# MCU.net
KiCad netlist of a schematic drawn in Altium Designer
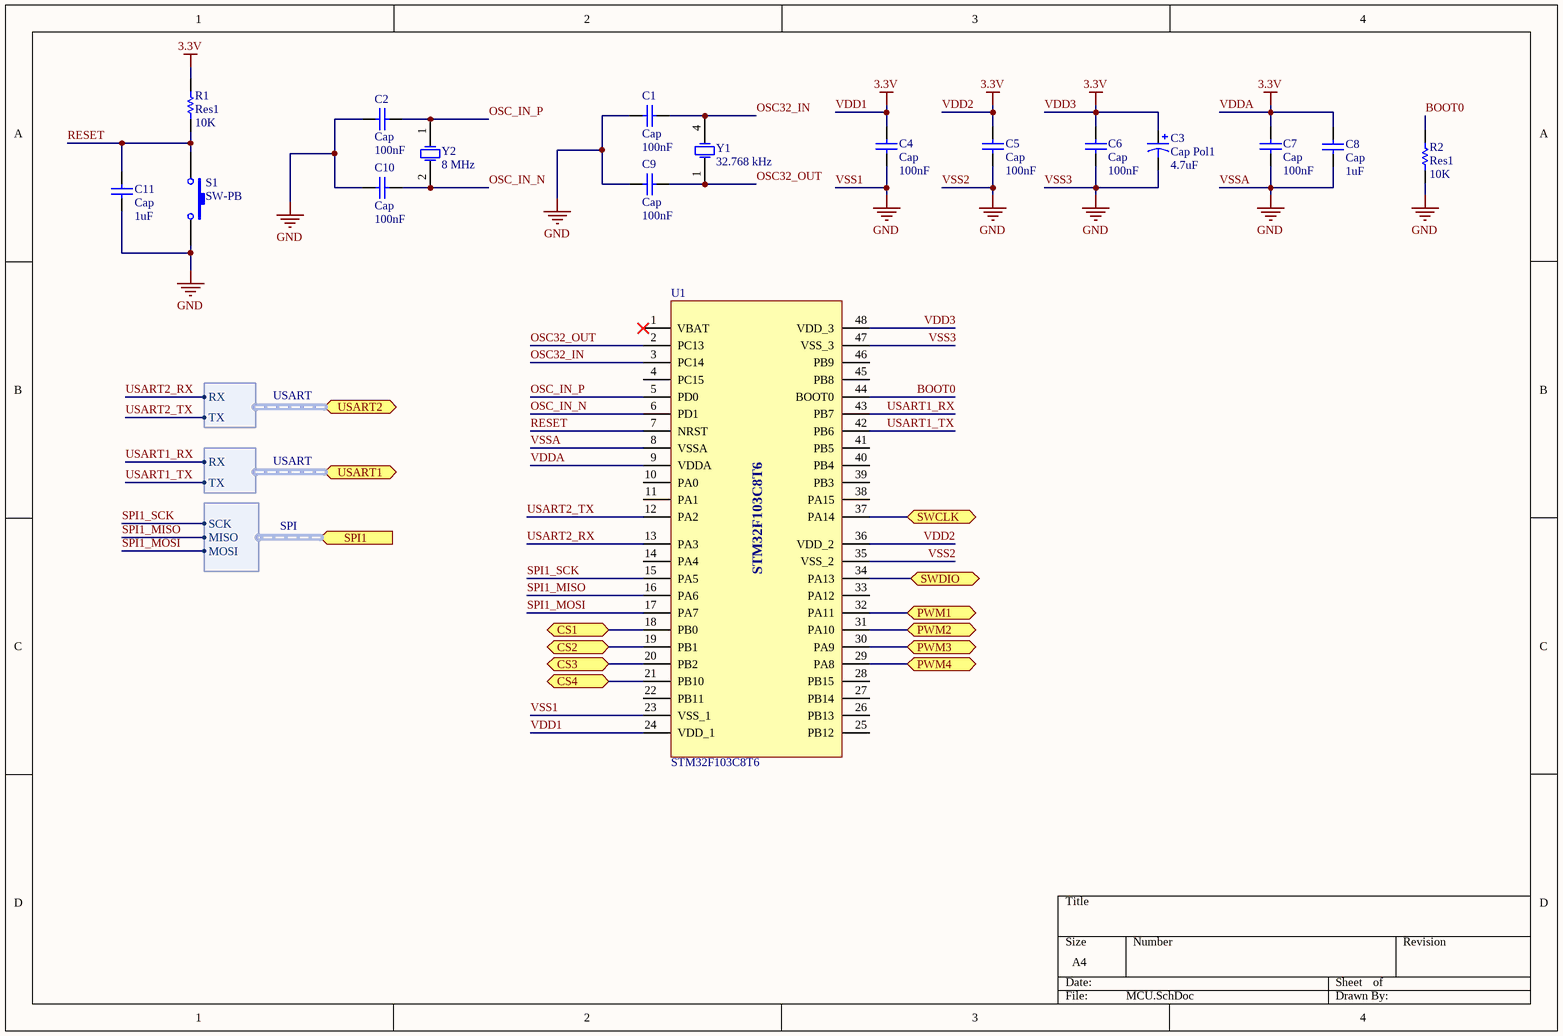
[diagram p0: MCU.SchDoc]

(export (version "E")
  (design (tool "Eeschema 10.0.6"))
  (components
    (comp (ref "C1")
      (value "Cap")
      (footprint "0805-CAP")
      (description "Capacitor")
      (fields (field (name "ALTIUM_VALUE") "100nF") (field (name "PUBLISHER") "Altium Limited"))
      (libsource (lib "Miscellaneous Devices") (part "Cap"))
    )
    (comp (ref "C2")
      (value "Cap")
      (footprint "0805-CAP")
      (description "Capacitor")
      (fields (field (name "ALTIUM_VALUE") "100nF") (field (name "PUBLISHER") "Altium Limited"))
      (libsource (lib "Miscellaneous Devices") (part "Cap"))
    )
    (comp (ref "C3")
      (value "Cap Pol1")
      (footprint "Tantalum A-Case")
      (description "Polarized Capacitor (Radial)")
      (fields (field (name "ALTIUM_VALUE") "4.7uF") (field (name "PUBLISHER") "Altium Limited"))
      (libsource (lib "Miscellaneous Devices") (part "Cap Pol1"))
    )
    (comp (ref "C4")
      (value "Cap")
      (footprint "0805-CAP")
      (description "Capacitor")
      (fields (field (name "ALTIUM_VALUE") "100nF") (field (name "PUBLISHER") "Altium Limited"))
      (libsource (lib "Miscellaneous Devices") (part "Cap"))
    )
    (comp (ref "C5")
      (value "Cap")
      (footprint "0805-CAP")
      (description "Capacitor")
      (fields (field (name "ALTIUM_VALUE") "100nF") (field (name "PUBLISHER") "Altium Limited"))
      (libsource (lib "Miscellaneous Devices") (part "Cap"))
    )
    (comp (ref "C6")
      (value "Cap")
      (footprint "0805-CAP")
      (description "Capacitor")
      (fields (field (name "ALTIUM_VALUE") "100nF") (field (name "PUBLISHER") "Altium Limited"))
      (libsource (lib "Miscellaneous Devices") (part "Cap"))
    )
    (comp (ref "C7")
      (value "Cap")
      (footprint "0805-CAP")
      (description "Capacitor")
      (fields (field (name "ALTIUM_VALUE") "100nF") (field (name "PUBLISHER") "Altium Limited"))
      (libsource (lib "Miscellaneous Devices") (part "Cap"))
    )
    (comp (ref "C8")
      (value "Cap")
      (footprint "0805-CAP")
      (description "Capacitor")
      (fields (field (name "ALTIUM_VALUE") "1uF") (field (name "PUBLISHER") "Altium Limited"))
      (libsource (lib "Miscellaneous Devices") (part "Cap"))
    )
    (comp (ref "C9")
      (value "Cap")
      (footprint "0805-CAP")
      (description "Capacitor")
      (fields (field (name "ALTIUM_VALUE") "100nF") (field (name "PUBLISHER") "Altium Limited"))
      (libsource (lib "Miscellaneous Devices") (part "Cap"))
    )
    (comp (ref "C10")
      (value "Cap")
      (footprint "0805-CAP")
      (description "Capacitor")
      (fields (field (name "ALTIUM_VALUE") "100nF") (field (name "PUBLISHER") "Altium Limited"))
      (libsource (lib "Miscellaneous Devices") (part "Cap"))
    )
    (comp (ref "C11")
      (value "Cap")
      (footprint "0805-CAP")
      (description "Capacitor")
      (fields (field (name "ALTIUM_VALUE") "1uF") (field (name "PUBLISHER") "Altium Limited"))
      (libsource (lib "Miscellaneous Devices") (part "Cap"))
    )
    (comp (ref "R1")
      (value "Res1")
      (footprint "0805-RES")
      (description "Resistor")
      (fields (field (name "ALTIUM_VALUE") "10K") (field (name "PUBLISHER") "Altium Limited"))
      (libsource (lib "Miscellaneous Devices") (part "Res1"))
    )
    (comp (ref "R2")
      (value "Res1")
      (footprint "0805-RES")
      (description "Resistor")
      (fields (field (name "ALTIUM_VALUE") "10K") (field (name "PUBLISHER") "Altium Limited"))
      (libsource (lib "Miscellaneous Devices") (part "Res1"))
    )
    (comp (ref "S1")
      (value "SW-PB")
      (footprint "3x6x2.5mm Tacticle Push Button")
      (description "Switch")
      (fields (field (name "PUBLISHER") "Altium Limited"))
      (libsource (lib "Miscellaneous Devices") (part "SW-PB"))
    )
    (comp (ref "U1")
      (value "STM32F103C8T6")
      (footprint "LQFP-48")
      (description "STM32F103C8T6 LQPF-48")
      (libsource (lib "MCU-Schematics") (part "STM32F103C8T6-LQPF48"))
    )
    (comp (ref "Y1")
      (value "32.768 kHz")
      (footprint "MC-306 SMD")
      (description "Crystal Oscillator")
      (fields (field (name "PUBLISHER") "Altium Limited"))
      (libsource (lib "Miscellaneous Devices") (part "XTAL"))
    )
    (comp (ref "Y2")
      (value "8 MHz")
      (footprint "HC49 Crystal SMD")
      (description "Crystal Oscillator")
      (fields (field (name "PUBLISHER") "Altium Limited"))
      (libsource (lib "") (part "XTAL_1"))
    )
  )
  (nets
    (net (code "3") (name "/BOOT0") (class "Default")
      (node (ref "R2") (pin "2") (pinfunction "2_2") (pintype "passive"))
      (node (ref "U1") (pin "44") (pinfunction "BOOT0_44") (pintype "passive"))
    )
    (net (code "4") (name "/CS1") (class "Default")
      (node (ref "U1") (pin "18") (pinfunction "PB0_18") (pintype "passive"))
    )
    (net (code "5") (name "/CS2") (class "Default")
      (node (ref "U1") (pin "19") (pinfunction "PB1_19") (pintype "passive"))
    )
    (net (code "6") (name "/CS3") (class "Default")
      (node (ref "U1") (pin "20") (pinfunction "PB2_20") (pintype "passive"))
    )
    (net (code "7") (name "/CS4") (class "Default")
      (node (ref "U1") (pin "21") (pinfunction "PB10_21") (pintype "passive"))
    )
    (net (code "8") (name "/OSC32_IN") (class "Default")
      (node (ref "C1") (pin "1") (pinfunction "1_1") (pintype "passive"))
      (node (ref "U1") (pin "3") (pinfunction "PC14_3") (pintype "passive"))
      (node (ref "Y1") (pin "4") (pinfunction "OSC2_4") (pintype "passive"))
    )
    (net (code "9") (name "/OSC32_OUT") (class "Default")
      (node (ref "C9") (pin "1") (pinfunction "1_1") (pintype "passive"))
      (node (ref "U1") (pin "2") (pinfunction "PC13_2") (pintype "passive"))
      (node (ref "Y1") (pin "1") (pinfunction "OSC1_1") (pintype "passive"))
    )
    (net (code "10") (name "/OSC_IN_N") (class "Default")
      (node (ref "C10") (pin "1") (pinfunction "1_1") (pintype "passive"))
      (node (ref "U1") (pin "6") (pinfunction "PD1_6") (pintype "passive"))
      (node (ref "Y2") (pin "2") (pinfunction "OSC2_2") (pintype "passive"))
    )
    (net (code "11") (name "/OSC_IN_P") (class "Default")
      (node (ref "C2") (pin "1") (pinfunction "1_1") (pintype "passive"))
      (node (ref "U1") (pin "5") (pinfunction "PD0_5") (pintype "passive"))
      (node (ref "Y2") (pin "1") (pinfunction "OSC1_1") (pintype "passive"))
    )
    (net (code "12") (name "/PWM1") (class "Default")
      (node (ref "U1") (pin "32") (pinfunction "PA11_32") (pintype "passive"))
    )
    (net (code "13") (name "/PWM2") (class "Default")
      (node (ref "U1") (pin "31") (pinfunction "PA10_31") (pintype "passive"))
    )
    (net (code "14") (name "/PWM3") (class "Default")
      (node (ref "U1") (pin "30") (pinfunction "PA9_30") (pintype "passive"))
    )
    (net (code "15") (name "/PWM4") (class "Default")
      (node (ref "U1") (pin "29") (pinfunction "PA8_29") (pintype "passive"))
    )
    (net (code "16") (name "/RESET") (class "Default")
      (node (ref "C11") (pin "2") (pinfunction "2_2") (pintype "passive"))
      (node (ref "R1") (pin "1") (pinfunction "1_1") (pintype "passive"))
      (node (ref "S1") (pin "1") (pinfunction "1_1") (pintype "passive"))
      (node (ref "U1") (pin "7") (pinfunction "NRST_7") (pintype "passive"))
    )
    (net (code "17") (name "/SPI1_MISO") (class "Default")
      (node (ref "U1") (pin "16") (pinfunction "PA6_16") (pintype "passive"))
    )
    (net (code "18") (name "/SPI1_MOSI") (class "Default")
      (node (ref "U1") (pin "17") (pinfunction "PA7_17") (pintype "passive"))
    )
    (net (code "19") (name "/SPI1_SCK") (class "Default")
      (node (ref "U1") (pin "15") (pinfunction "PA5_15") (pintype "passive"))
    )
    (net (code "20") (name "/SWCLK") (class "Default")
      (node (ref "U1") (pin "37") (pinfunction "PA14_37") (pintype "passive"))
    )
    (net (code "21") (name "/SWDIO") (class "Default")
      (node (ref "U1") (pin "34") (pinfunction "PA13_34") (pintype "passive"))
    )
    (net (code "22") (name "/USART1_RX") (class "Default")
      (node (ref "U1") (pin "43") (pinfunction "PB7_43") (pintype "passive"))
    )
    (net (code "23") (name "/USART1_TX") (class "Default")
      (node (ref "U1") (pin "42") (pinfunction "PB6_42") (pintype "passive"))
    )
    (net (code "24") (name "/USART2_RX") (class "Default")
      (node (ref "U1") (pin "13") (pinfunction "PA3_13") (pintype "passive"))
    )
    (net (code "25") (name "/USART2_TX") (class "Default")
      (node (ref "U1") (pin "12") (pinfunction "PA2_12") (pintype "passive"))
    )
    (net (code "28") (name "3.3V") (class "Default")
      (node (ref "C3") (pin "1") (pinfunction "1_1") (pintype "passive"))
      (node (ref "C4") (pin "2") (pinfunction "2_2") (pintype "passive"))
      (node (ref "C5") (pin "2") (pinfunction "2_2") (pintype "passive"))
      (node (ref "C6") (pin "2") (pinfunction "2_2") (pintype "passive"))
      (node (ref "C7") (pin "2") (pinfunction "2_2") (pintype "passive"))
      (node (ref "C8") (pin "2") (pinfunction "2_2") (pintype "passive"))
      (node (ref "R1") (pin "2") (pinfunction "2_2") (pintype "passive"))
      (node (ref "U1") (pin "24") (pinfunction "VDD_1_24") (pintype "passive"))
      (node (ref "U1") (pin "36") (pinfunction "VDD_2_36") (pintype "passive"))
      (node (ref "U1") (pin "48") (pinfunction "VDD_3_48") (pintype "passive"))
      (node (ref "U1") (pin "9") (pinfunction "VDDA_9") (pintype "passive"))
    )
    (net (code "29") (name "GND") (class "Default")
      (node (ref "C1") (pin "2") (pinfunction "2_2") (pintype "passive"))
      (node (ref "C10") (pin "2") (pinfunction "2_2") (pintype "passive"))
      (node (ref "C11") (pin "1") (pinfunction "1_1") (pintype "passive"))
      (node (ref "C2") (pin "2") (pinfunction "2_2") (pintype "passive"))
      (node (ref "C3") (pin "2") (pinfunction "2_2") (pintype "passive"))
      (node (ref "C4") (pin "1") (pinfunction "1_1") (pintype "passive"))
      (node (ref "C5") (pin "1") (pinfunction "1_1") (pintype "passive"))
      (node (ref "C6") (pin "1") (pinfunction "1_1") (pintype "passive"))
      (node (ref "C7") (pin "1") (pinfunction "1_1") (pintype "passive"))
      (node (ref "C8") (pin "1") (pinfunction "1_1") (pintype "passive"))
      (node (ref "C9") (pin "2") (pinfunction "2_2") (pintype "passive"))
      (node (ref "R2") (pin "1") (pinfunction "1_1") (pintype "passive"))
      (node (ref "S1") (pin "2") (pinfunction "2_2") (pintype "passive"))
      (node (ref "U1") (pin "23") (pinfunction "VSS_1_23") (pintype "passive"))
      (node (ref "U1") (pin "35") (pinfunction "VSS_2_35") (pintype "passive"))
      (node (ref "U1") (pin "47") (pinfunction "VSS_3_47") (pintype "passive"))
      (node (ref "U1") (pin "8") (pinfunction "VSSA_8") (pintype "passive"))
    )
    (net (code "30") (name "unconnected-(U1-PA0-Pad10)") (class "Default")
      (node (ref "U1") (pin "10") (pinfunction "PA0_10") (pintype "passive"))
    )
    (net (code "31") (name "unconnected-(U1-PA1-Pad11)") (class "Default")
      (node (ref "U1") (pin "11") (pinfunction "PA1_11") (pintype "passive"))
    )
    (net (code "32") (name "unconnected-(U1-PA4-Pad14)") (class "Default")
      (node (ref "U1") (pin "14") (pinfunction "PA4_14") (pintype "passive"))
    )
    (net (code "33") (name "unconnected-(U1-PA12-Pad33)") (class "Default")
      (node (ref "U1") (pin "33") (pinfunction "PA12_33") (pintype "passive"))
    )
    (net (code "34") (name "unconnected-(U1-PA15-Pad38)") (class "Default")
      (node (ref "U1") (pin "38") (pinfunction "PA15_38") (pintype "passive"))
    )
    (net (code "35") (name "unconnected-(U1-PB3-Pad39)") (class "Default")
      (node (ref "U1") (pin "39") (pinfunction "PB3_39") (pintype "passive"))
    )
    (net (code "36") (name "unconnected-(U1-PB4-Pad40)") (class "Default")
      (node (ref "U1") (pin "40") (pinfunction "PB4_40") (pintype "passive"))
    )
    (net (code "37") (name "unconnected-(U1-PB5-Pad41)") (class "Default")
      (node (ref "U1") (pin "41") (pinfunction "PB5_41") (pintype "passive"))
    )
    (net (code "38") (name "unconnected-(U1-PB8-Pad45)") (class "Default")
      (node (ref "U1") (pin "45") (pinfunction "PB8_45") (pintype "passive"))
    )
    (net (code "39") (name "unconnected-(U1-PB9-Pad46)") (class "Default")
      (node (ref "U1") (pin "46") (pinfunction "PB9_46") (pintype "passive"))
    )
    (net (code "40") (name "unconnected-(U1-PB11-Pad22)") (class "Default")
      (node (ref "U1") (pin "22") (pinfunction "PB11_22") (pintype "passive"))
    )
    (net (code "41") (name "unconnected-(U1-PB12-Pad25)") (class "Default")
      (node (ref "U1") (pin "25") (pinfunction "PB12_25") (pintype "passive"))
    )
    (net (code "42") (name "unconnected-(U1-PB13-Pad26)") (class "Default")
      (node (ref "U1") (pin "26") (pinfunction "PB13_26") (pintype "passive"))
    )
    (net (code "43") (name "unconnected-(U1-PB14-Pad27)") (class "Default")
      (node (ref "U1") (pin "27") (pinfunction "PB14_27") (pintype "passive"))
    )
    (net (code "44") (name "unconnected-(U1-PB15-Pad28)") (class "Default")
      (node (ref "U1") (pin "28") (pinfunction "PB15_28") (pintype "passive"))
    )
    (net (code "45") (name "unconnected-(U1-PC15-Pad4)") (class "Default")
      (node (ref "U1") (pin "4") (pinfunction "PC15_4") (pintype "passive"))
    )
    (net (code "46") (name "unconnected-(U1-VBAT-Pad1)") (class "Default")
      (node (ref "U1") (pin "1") (pinfunction "VBAT_1") (pintype "passive+no_connect"))
    )
  )
)
